# RDN_3103.net
KiCad netlist of a schematic drawn in EAGLE
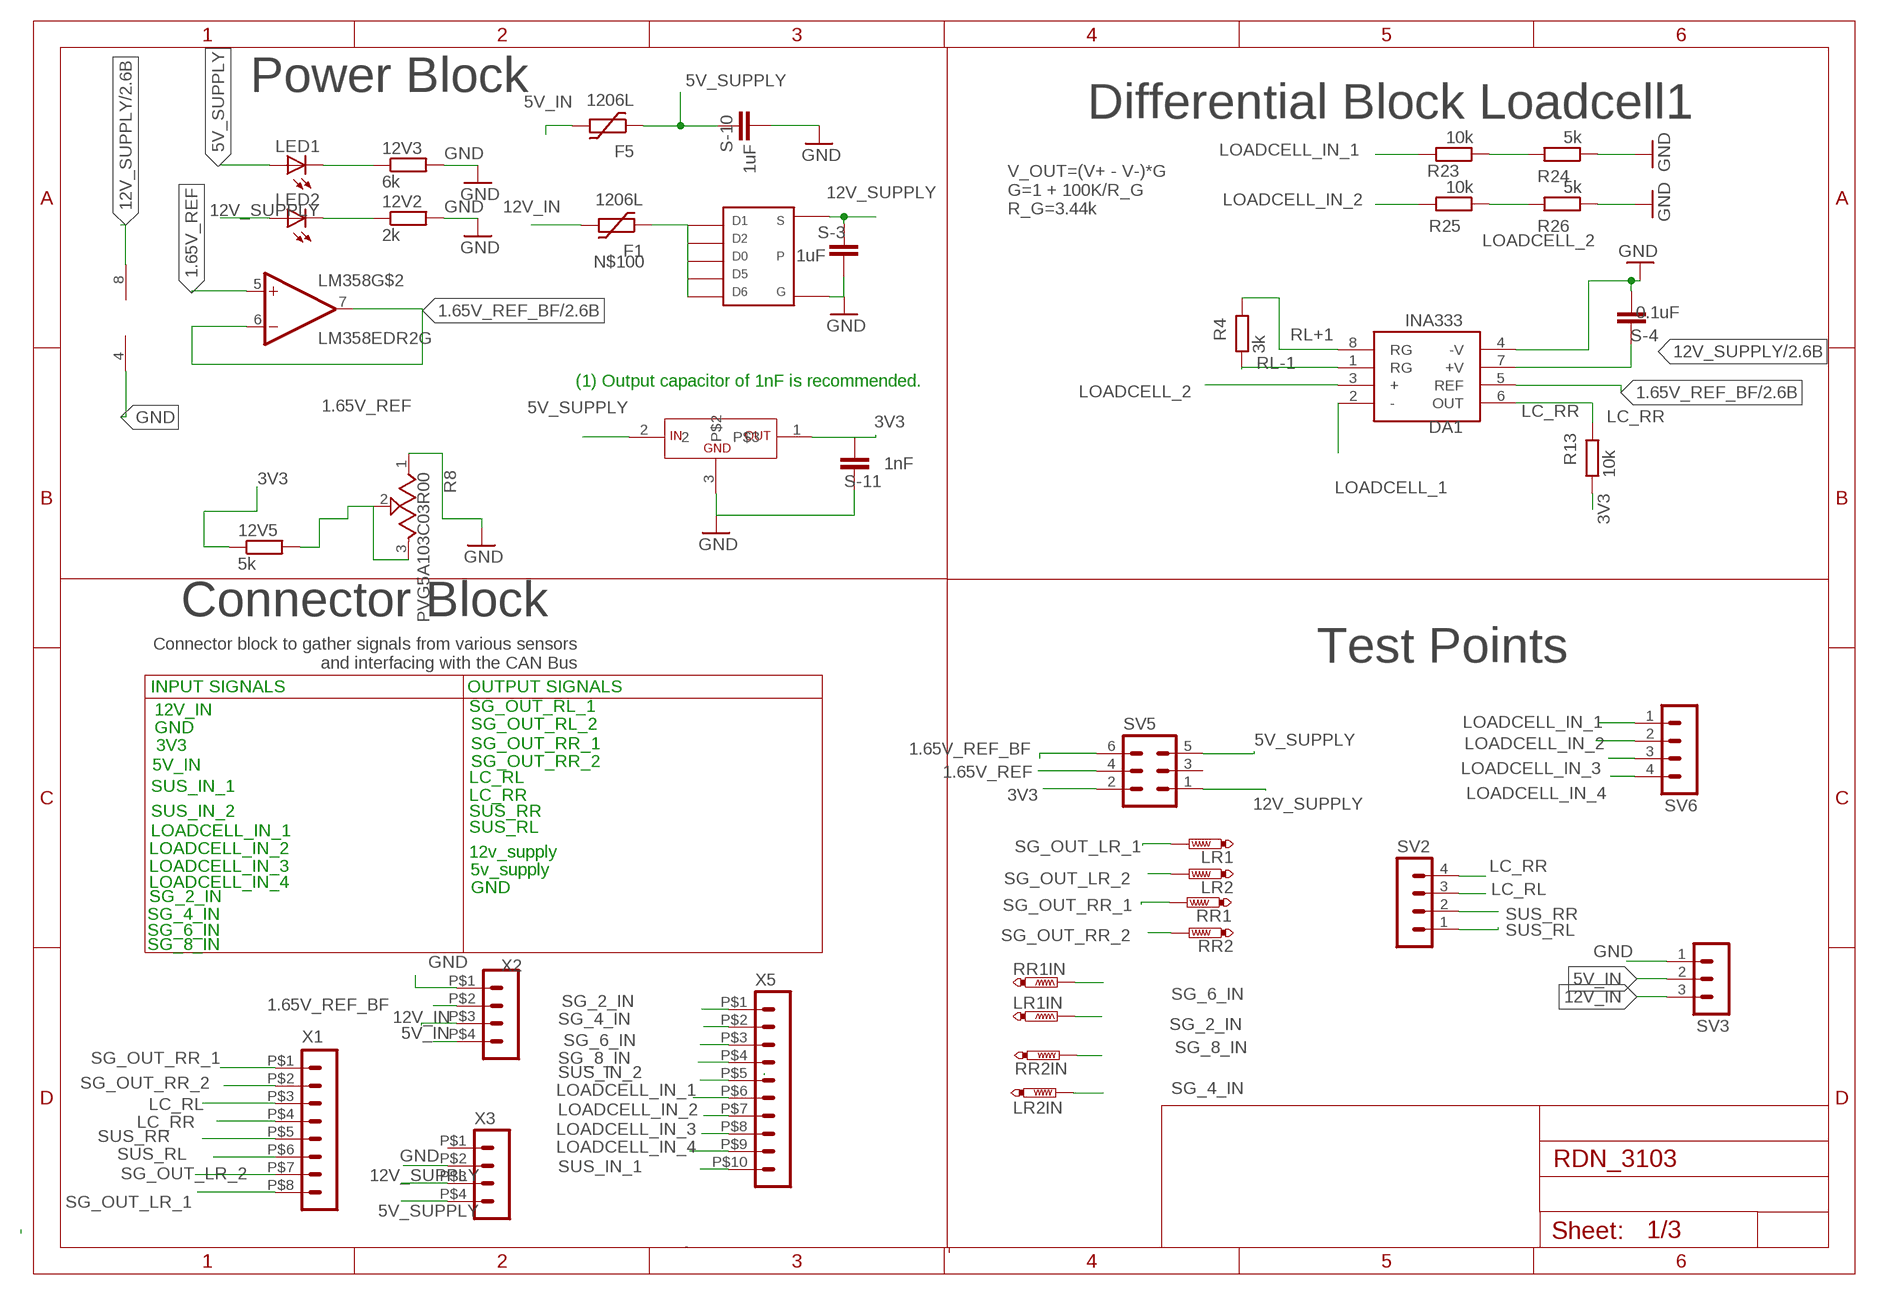
[diagram p0: schematic, sheet 1]
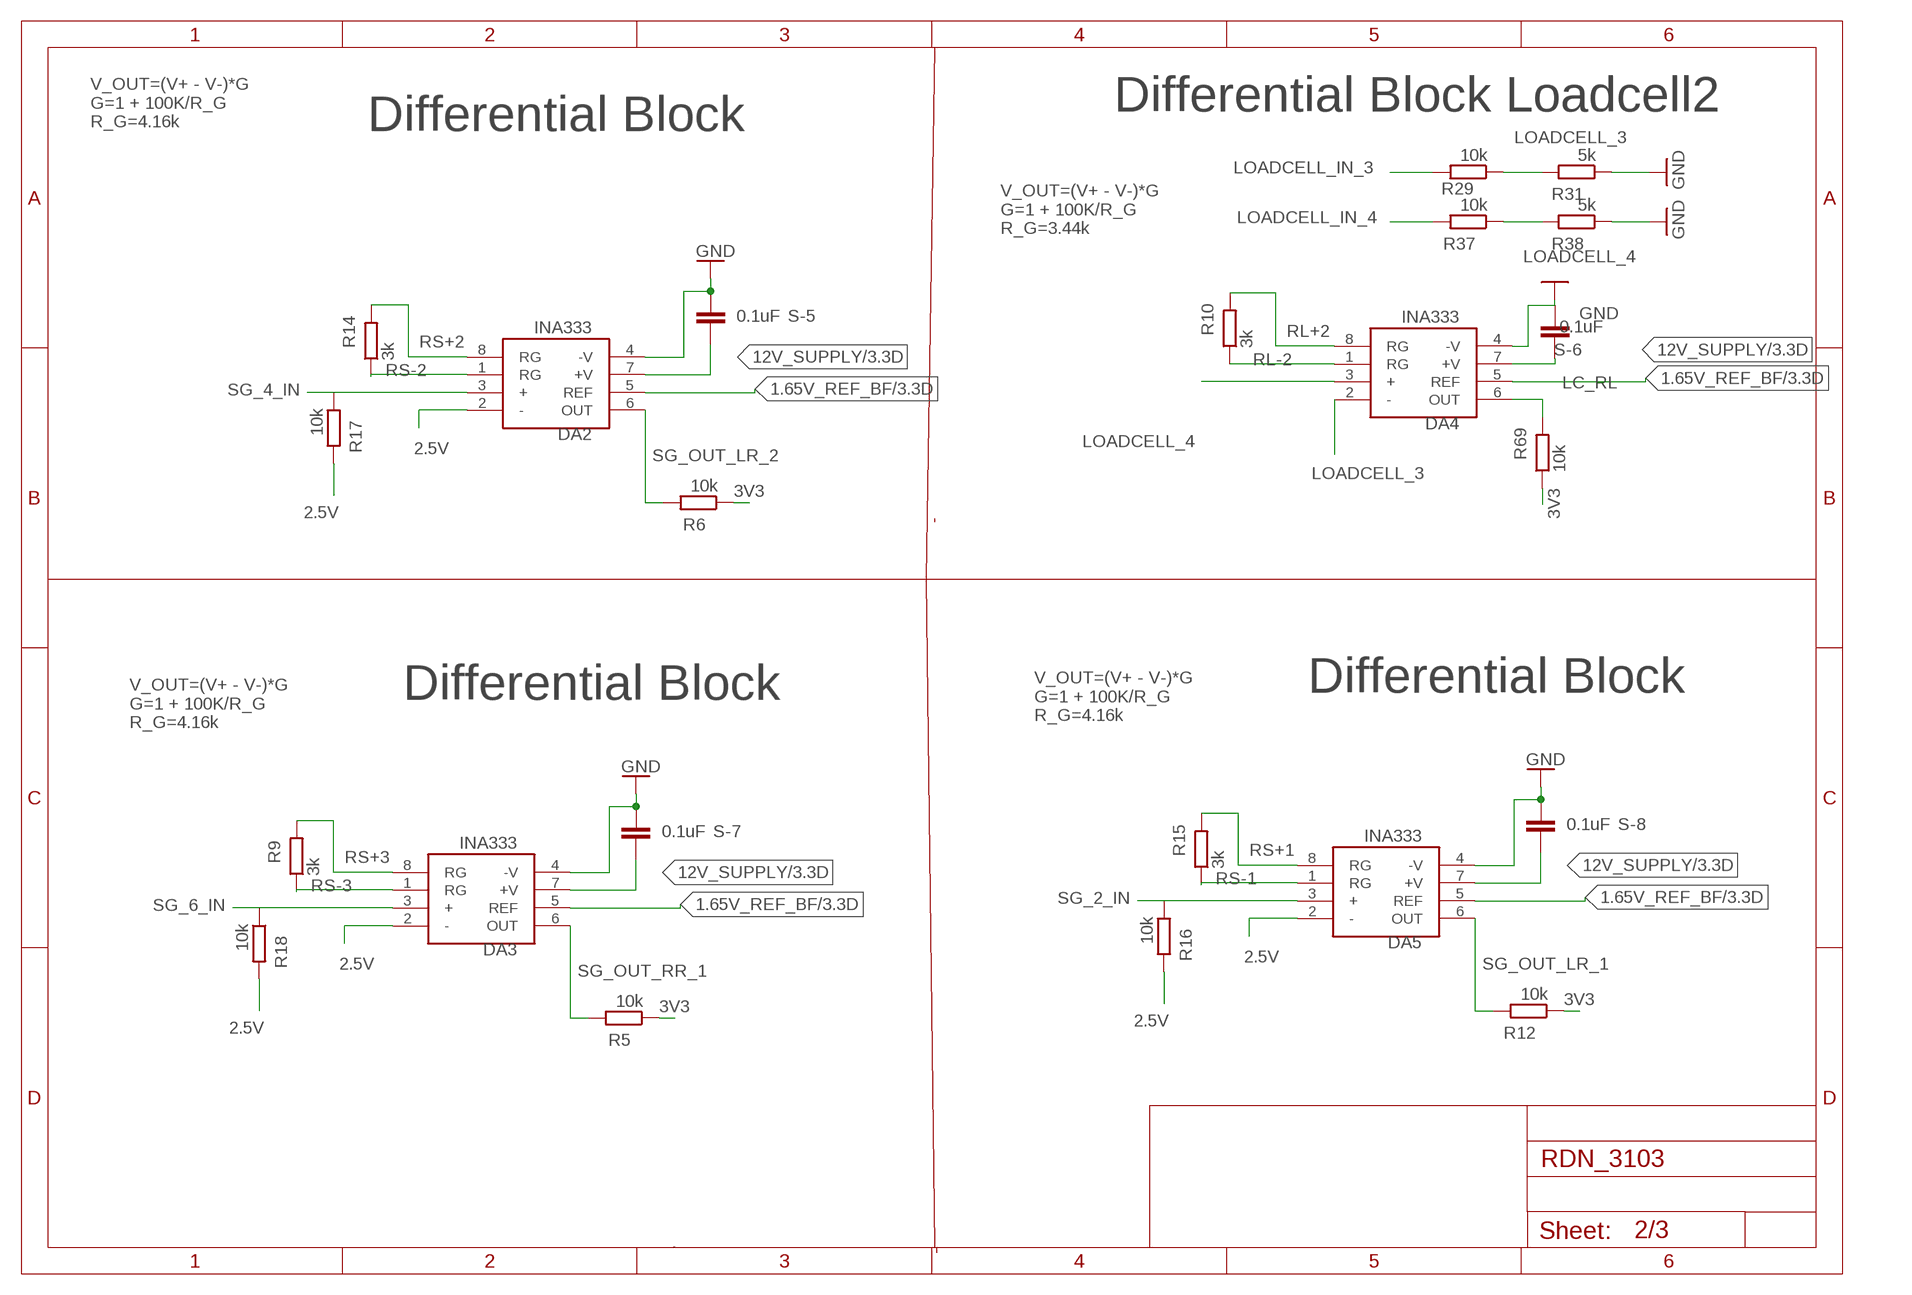
[diagram p1: schematic, sheet 2]
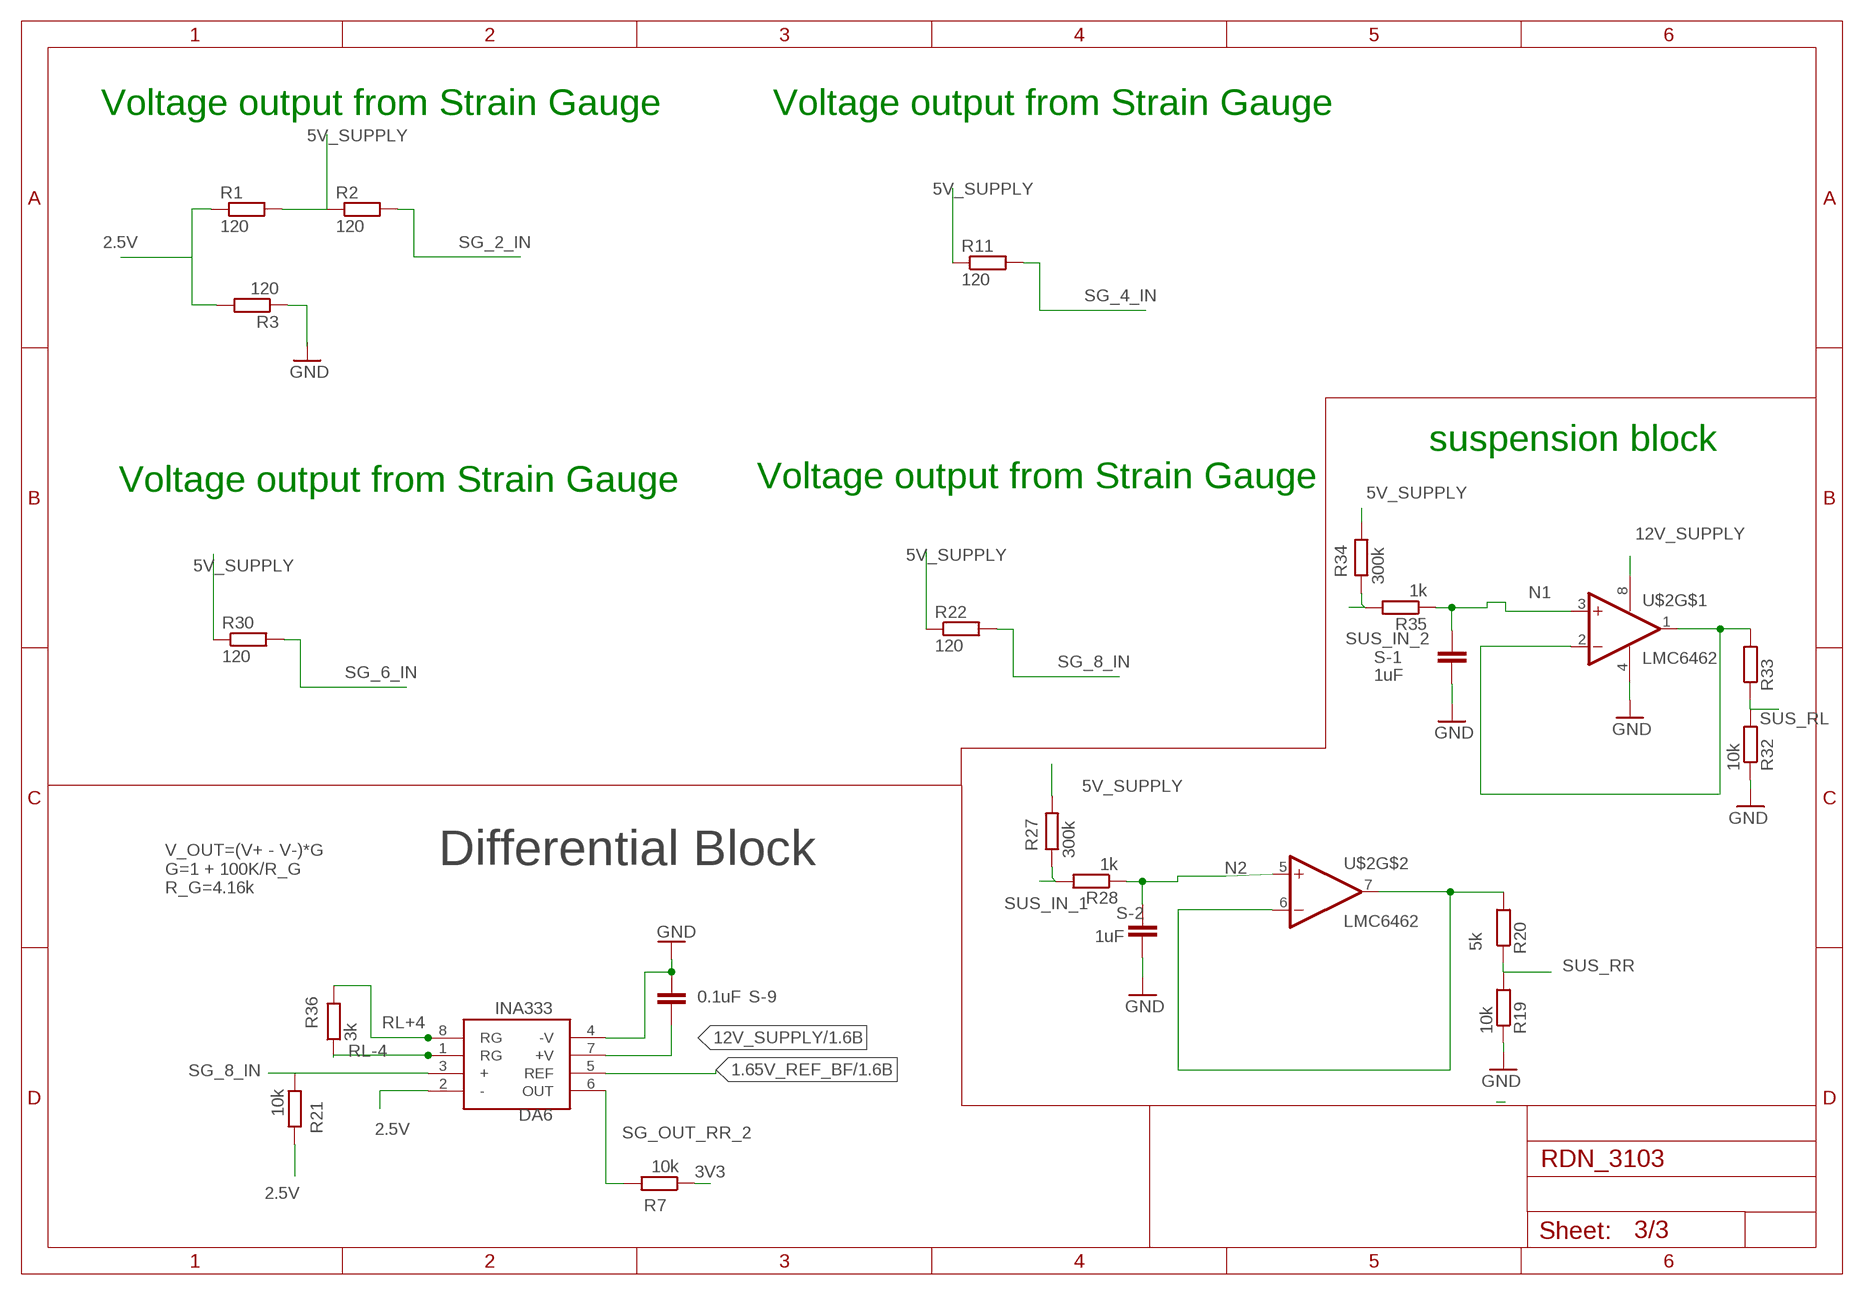
[diagram p2: schematic, sheet 3]

(export (version "E")
  (design (tool "Eeschema 10.0.6"))
  (components
    (comp (ref "DA2")
      (value "INA333")
      (footprint "eagle-import:MSOP8")
      (fields (field (name "MF") "Texas Instruments"))
      (libsource (lib "eagle-import") (part "INA333"))
    )
    (comp (ref "DA3")
      (value "INA333")
      (footprint "eagle-import:MSOP8")
      (fields (field (name "MF") "Texas Instruments"))
      (libsource (lib "eagle-import") (part "INA333"))
    )
    (comp (ref "DA4")
      (value "INA333")
      (footprint "eagle-import:MSOP8")
      (fields (field (name "MF") "Texas Instruments"))
      (libsource (lib "eagle-import") (part "INA333"))
    )
    (comp (ref "DA5")
      (value "INA333")
      (footprint "eagle-import:MSOP8")
      (fields (field (name "MF") "Texas Instruments"))
      (libsource (lib "eagle-import") (part "INA333"))
    )
    (comp (ref "R5")
      (value "10k")
      (footprint "eagle-import:R0805")
      (libsource (lib "eagle-import") (part "R-EU_R0805"))
    )
    (comp (ref "R6")
      (value "10k")
      (footprint "eagle-import:R0805")
      (libsource (lib "eagle-import") (part "R-EU_R0805"))
    )
    (comp (ref "R9")
      (value "3k")
      (footprint "eagle-import:R0805")
      (libsource (lib "eagle-import") (part "R-EU_R0805"))
    )
    (comp (ref "R10")
      (value "3k")
      (footprint "eagle-import:R0805")
      (libsource (lib "eagle-import") (part "R-EU_R0805"))
    )
    (comp (ref "R12")
      (value "10k")
      (footprint "eagle-import:R0805")
      (libsource (lib "eagle-import") (part "R-EU_R0805"))
    )
    (comp (ref "R14")
      (value "3k")
      (footprint "eagle-import:R0805")
      (libsource (lib "eagle-import") (part "R-EU_R0805"))
    )
    (comp (ref "R15")
      (value "3k")
      (footprint "eagle-import:R0805")
      (libsource (lib "eagle-import") (part "R-EU_R0805"))
    )
    (comp (ref "R16")
      (value "10k")
      (footprint "eagle-import:R0805")
      (libsource (lib "eagle-import") (part "R-EU_R0805"))
    )
    (comp (ref "R17")
      (value "10k")
      (footprint "eagle-import:R0805")
      (libsource (lib "eagle-import") (part "R-EU_R0805"))
    )
    (comp (ref "R18")
      (value "10k")
      (footprint "eagle-import:R0805")
      (libsource (lib "eagle-import") (part "R-EU_R0805"))
    )
    (comp (ref "R29")
      (value "10k")
      (footprint "eagle-import:R0805")
      (libsource (lib "eagle-import") (part "R-EU_R0805"))
    )
    (comp (ref "R31")
      (value "5k")
      (footprint "eagle-import:R0805")
      (libsource (lib "eagle-import") (part "R-EU_R0805"))
    )
    (comp (ref "R37")
      (value "10k")
      (footprint "eagle-import:R0805")
      (libsource (lib "eagle-import") (part "R-EU_R0805"))
    )
    (comp (ref "R38")
      (value "5k")
      (footprint "eagle-import:R0805")
      (libsource (lib "eagle-import") (part "R-EU_R0805"))
    )
    (comp (ref "R69")
      (value "10k")
      (footprint "eagle-import:R0805")
      (libsource (lib "eagle-import") (part "R-EU_R0805"))
    )
    (comp (ref "S-5")
      (value "0.1uF")
      (footprint "eagle-import:C0805")
      (libsource (lib "eagle-import") (part "C-EUC0805"))
    )
    (comp (ref "S-6")
      (value "0.1uF")
      (footprint "eagle-import:C0805")
      (libsource (lib "eagle-import") (part "C-EUC0805"))
    )
    (comp (ref "S-7")
      (value "0.1uF")
      (footprint "eagle-import:C0805")
      (libsource (lib "eagle-import") (part "C-EUC0805"))
    )
    (comp (ref "S-8")
      (value "0.1uF")
      (footprint "eagle-import:C0805")
      (libsource (lib "eagle-import") (part "C-EUC0805"))
    )
    (comp (ref "12V2")
      (value "2k")
      (footprint "eagle-import:R0805")
      (libsource (lib "eagle-import") (part "rcl_R-EU_R0805"))
    )
    (comp (ref "12V3")
      (value "6k")
      (footprint "eagle-import:R0805")
      (libsource (lib "eagle-import") (part "rcl_R-EU_R0805"))
    )
    (comp (ref "12V5")
      (value "5k")
      (footprint "eagle-import:R0805")
      (libsource (lib "eagle-import") (part "rcl_R-EU_R0805"))
    )
    (comp (ref "DA1")
      (value "INA333")
      (footprint "eagle-import:MSOP8")
      (fields (field (name "MF") "Texas Instruments"))
      (libsource (lib "eagle-import") (part "INA333"))
    )
    (comp (ref "F1")
      (value "1206L")
      (footprint "eagle-import:1206L")
      (libsource (lib "eagle-import") (part "1206L"))
    )
    (comp (ref "F5")
      (value "1206L")
      (footprint "eagle-import:1206L")
      (libsource (lib "eagle-import") (part "1206L"))
    )
    (comp (ref "LED1")
      (value "LEDCHIPLED_1206")
      (footprint "eagle-import:CHIPLED_1206")
      (libsource (lib "eagle-import") (part "LEDCHIPLED_1206"))
    )
    (comp (ref "LED2")
      (value "LEDCHIPLED_1206")
      (footprint "eagle-import:CHIPLED_1206")
      (fields (field (name "SPICEPREFIX") "L"))
      (libsource (lib "eagle-import") (part "LEDCHIPLED_1206"))
    )
    (comp (ref "LM358")
      (value "LM358EDR2G")
      (footprint "eagle-import:SOIC-8")
      (libsource (lib "eagle-import") (part "LM358EDR2G"))
    )
    (comp (ref "LR1")
      (value "PTR1PAD1-13")
      (footprint "eagle-import:P1-13")
      (libsource (lib "eagle-import") (part "PTR1PAD1-13"))
    )
    (comp (ref "LR1IN")
      (value "PTR1PAD1-13")
      (footprint "eagle-import:P1-13")
      (libsource (lib "eagle-import") (part "PTR1PAD1-13"))
    )
    (comp (ref "LR2")
      (value "PTR1PAD1-13")
      (footprint "eagle-import:P1-13")
      (libsource (lib "eagle-import") (part "PTR1PAD1-13"))
    )
    (comp (ref "LR2IN")
      (value "PTR1PAD1-13")
      (footprint "eagle-import:P1-13")
      (libsource (lib "eagle-import") (part "PTR1PAD1-13"))
    )
    (comp (ref "R4")
      (value "3k")
      (footprint "eagle-import:R0805")
      (libsource (lib "eagle-import") (part "R-EU_R0805"))
    )
    (comp (ref "R8")
      (value "PVG5A103C03R00")
      (footprint "eagle-import:TRIM_PVG5A103C03R00")
      (fields (field (name "MF") "Bourns"))
      (libsource (lib "eagle-import") (part "PVG5A103C03R00"))
    )
    (comp (ref "R13")
      (value "10k")
      (footprint "eagle-import:R0805")
      (libsource (lib "eagle-import") (part "R-EU_R0805"))
    )
    (comp (ref "R23")
      (value "10k")
      (footprint "eagle-import:R0805")
      (libsource (lib "eagle-import") (part "R-EU_R0805"))
    )
    (comp (ref "R24")
      (value "5k")
      (footprint "eagle-import:R0805")
      (libsource (lib "eagle-import") (part "R-EU_R0805"))
    )
    (comp (ref "R25")
      (value "10k")
      (footprint "eagle-import:R0805")
      (libsource (lib "eagle-import") (part "R-EU_R0805"))
    )
    (comp (ref "R26")
      (value "5k")
      (footprint "eagle-import:R0805")
      (libsource (lib "eagle-import") (part "R-EU_R0805"))
    )
    (comp (ref "RR1")
      (value "PTR1PAD1-13")
      (footprint "eagle-import:P1-13")
      (libsource (lib "eagle-import") (part "PTR1PAD1-13"))
    )
    (comp (ref "RR1IN")
      (value "PTR1PAD1-13")
      (footprint "eagle-import:P1-13")
      (libsource (lib "eagle-import") (part "PTR1PAD1-13"))
    )
    (comp (ref "RR2")
      (value "PTR1PAD1-13")
      (footprint "eagle-import:P1-13")
      (libsource (lib "eagle-import") (part "PTR1PAD1-13"))
    )
    (comp (ref "RR2IN")
      (value "PTR1PAD1-13")
      (footprint "eagle-import:P1-13")
      (libsource (lib "eagle-import") (part "PTR1PAD1-13"))
    )
    (comp (ref "S-3")
      (value "1uF")
      (footprint "eagle-import:C0805")
      (libsource (lib "eagle-import") (part "C-EUC0805"))
    )
    (comp (ref "S-4")
      (value "0.1uF")
      (footprint "eagle-import:C0805")
      (libsource (lib "eagle-import") (part "C-EUC0805"))
    )
    (comp (ref "S-10")
      (value "1uF")
      (footprint "eagle-import:C0805")
      (libsource (lib "eagle-import") (part "C-EUC0805"))
    )
    (comp (ref "S-11")
      (value "1nF")
      (footprint "eagle-import:C0805")
      (libsource (lib "eagle-import") (part "C-EUC0805"))
    )
    (comp (ref "SV2")
      (value "MA04-1")
      (footprint "eagle-import:MA04-1")
      (libsource (lib "eagle-import") (part "MA04-1"))
    )
    (comp (ref "SV3")
      (value "MA03-1")
      (footprint "eagle-import:MA03-1")
      (libsource (lib "eagle-import") (part "MA03-1"))
    )
    (comp (ref "SV5")
      (value "MA03-2")
      (footprint "eagle-import:MA03-2")
      (libsource (lib "eagle-import") (part "MA03-2"))
    )
    (comp (ref "SV6")
      (value "MA04-1")
      (footprint "eagle-import:MA04-1")
      (libsource (lib "eagle-import") (part "MA04-1"))
    )
    (comp (ref "U$1")
      (value "TSOP-6_PMOS")
      (footprint "eagle-import:TSOP-6_PMOS")
      (libsource (lib "eagle-import") (part "TSOP-6_PMOS"))
    )
    (comp (ref "U$3")
      (value "3V3_REGULATOR")
      (footprint "eagle-import:SOT-23")
      (libsource (lib "eagle-import") (part "3V3_REGULATOR"))
    )
    (comp (ref "X1")
      (value "HEADER_POS8_43045-0800")
      (footprint "eagle-import:43045-0800")
      (libsource (lib "eagle-import") (part "HEADER_POS8_?43045-0800"))
    )
    (comp (ref "X2")
      (value "HEADER_POS4_43045-0401")
      (footprint "eagle-import:43045-0400")
      (libsource (lib "eagle-import") (part "HEADER_POS4_?43045-0401"))
    )
    (comp (ref "X3")
      (value "HEADER_POS4_43045-0401")
      (footprint "eagle-import:43045-0400")
      (libsource (lib "eagle-import") (part "HEADER_POS4_?43045-0401"))
    )
    (comp (ref "X5")
      (value "HEADER_POS10_43045-1000")
      (footprint "eagle-import:43045-1000")
      (libsource (lib "eagle-import") (part "HEADER_POS10_?43045-1000"))
    )
    (comp (ref "DA6")
      (value "INA333")
      (footprint "eagle-import:MSOP8")
      (fields (field (name "MF") "Texas Instruments"))
      (libsource (lib "eagle-import") (part "INA333"))
    )
    (comp (ref "R1")
      (value "120")
      (footprint "eagle-import:R0805")
      (libsource (lib "eagle-import") (part "rcl_R-EU_R0805"))
    )
    (comp (ref "R2")
      (value "120")
      (footprint "eagle-import:R0805")
      (libsource (lib "eagle-import") (part "rcl_R-EU_R0805"))
    )
    (comp (ref "R3")
      (value "120")
      (footprint "eagle-import:R0805")
      (libsource (lib "eagle-import") (part "rcl_R-EU_R0805"))
    )
    (comp (ref "R7")
      (value "10k")
      (footprint "eagle-import:R0805")
      (libsource (lib "eagle-import") (part "R-EU_R0805"))
    )
    (comp (ref "R11")
      (value "120")
      (footprint "eagle-import:R0805")
      (libsource (lib "eagle-import") (part "rcl_R-EU_R0805"))
    )
    (comp (ref "R19")
      (value "10k")
      (footprint "eagle-import:R0805")
      (libsource (lib "eagle-import") (part "IIT_BOMBAY_Racing2_R-EU_R0805"))
    )
    (comp (ref "R20")
      (value "5k")
      (footprint "eagle-import:R0805")
      (libsource (lib "eagle-import") (part "IIT_BOMBAY_Racing2_R-EU_R0805"))
    )
    (comp (ref "R21")
      (value "10k")
      (footprint "eagle-import:R0805")
      (libsource (lib "eagle-import") (part "R-EU_R0805"))
    )
    (comp (ref "R22")
      (value "120")
      (footprint "eagle-import:R0805")
      (libsource (lib "eagle-import") (part "rcl_R-EU_R0805"))
    )
    (comp (ref "R27")
      (value "300k")
      (footprint "eagle-import:R0805")
      (libsource (lib "eagle-import") (part "IIT_BOMBAY_Racing2_R-EU_R0805"))
    )
    (comp (ref "R28")
      (value "1k")
      (footprint "eagle-import:R0805")
      (libsource (lib "eagle-import") (part "IIT_BOMBAY_Racing2_R-EU_R0805"))
    )
    (comp (ref "R30")
      (value "120")
      (footprint "eagle-import:R0805")
      (libsource (lib "eagle-import") (part "rcl_R-EU_R0805"))
    )
    (comp (ref "R32")
      (value "10k")
      (footprint "eagle-import:R0805")
      (libsource (lib "eagle-import") (part "IIT_BOMBAY_Racing2_R-EU_R0805"))
    )
    (comp (ref "R33")
      (value "5k")
      (footprint "eagle-import:R0805")
      (libsource (lib "eagle-import") (part "IIT_BOMBAY_Racing2_R-EU_R0805"))
    )
    (comp (ref "R34")
      (value "300k")
      (footprint "eagle-import:R0805")
      (libsource (lib "eagle-import") (part "IIT_BOMBAY_Racing2_R-EU_R0805"))
    )
    (comp (ref "R35")
      (value "1k")
      (footprint "eagle-import:R0805")
      (libsource (lib "eagle-import") (part "IIT_BOMBAY_Racing2_R-EU_R0805"))
    )
    (comp (ref "R36")
      (value "3k")
      (footprint "eagle-import:R0805")
      (libsource (lib "eagle-import") (part "R-EU_R0805"))
    )
    (comp (ref "S-1")
      (value "1uF")
      (footprint "eagle-import:C0805")
      (libsource (lib "eagle-import") (part "C-EUC0805"))
    )
    (comp (ref "S-2")
      (value "1uF")
      (footprint "eagle-import:C0805")
      (libsource (lib "eagle-import") (part "C-EUC0805"))
    )
    (comp (ref "S-9")
      (value "0.1uF")
      (footprint "eagle-import:C0805")
      (libsource (lib "eagle-import") (part "C-EUC0805"))
    )
    (comp (ref "U$2")
      (value "LMC6462")
      (footprint "eagle-import:S08")
      (libsource (lib "eagle-import") (part "LMC6462"))
    )
  )
  (nets
    (net (code "1") (name "1.65V_REF") (class "Default")
      (node (ref "12V5") (pin "2") (pinfunction "2_2") (pintype "passive"))
      (node (ref "LM358") (pin "5") (pinfunction "+IN_5") (pintype "input"))
      (node (ref "R8") (pin "2") (pinfunction "2_2") (pintype "passive"))
      (node (ref "R8") (pin "3") (pinfunction "3_3") (pintype "passive"))
      (node (ref "SV5") (pin "4") (pinfunction "4_4") (pintype "passive"))
    )
    (net (code "2") (name "1.65V_REF_BF") (class "Default")
      (node (ref "DA1") (pin "5") (pinfunction "REF_5") (pintype "bidirectional"))
      (node (ref "DA2") (pin "5") (pinfunction "REF_5") (pintype "bidirectional"))
      (node (ref "DA3") (pin "5") (pinfunction "REF_5") (pintype "bidirectional"))
      (node (ref "DA4") (pin "5") (pinfunction "REF_5") (pintype "bidirectional"))
      (node (ref "DA5") (pin "5") (pinfunction "REF_5") (pintype "bidirectional"))
      (node (ref "DA6") (pin "5") (pinfunction "REF_5") (pintype "bidirectional"))
      (node (ref "LM358") (pin "6") (pinfunction "-IN_6") (pintype "input"))
      (node (ref "LM358") (pin "7") (pinfunction "OUT_7") (pintype "output"))
      (node (ref "SV5") (pin "6") (pinfunction "6_6") (pintype "passive"))
      (node (ref "X2") (pin "P$2") (pinfunction "2_P$2") (pintype "passive"))
    )
    (net (code "3") (name "2.5V") (class "Default")
      (node (ref "DA2") (pin "2") (pinfunction "-_2") (pintype "bidirectional"))
      (node (ref "DA3") (pin "2") (pinfunction "-_2") (pintype "bidirectional"))
      (node (ref "DA5") (pin "2") (pinfunction "-_2") (pintype "bidirectional"))
      (node (ref "DA6") (pin "2") (pinfunction "-_2") (pintype "bidirectional"))
      (node (ref "R1") (pin "1") (pinfunction "1_1") (pintype "passive"))
      (node (ref "R16") (pin "2") (pinfunction "2_2") (pintype "passive"))
      (node (ref "R17") (pin "2") (pinfunction "2_2") (pintype "passive"))
      (node (ref "R18") (pin "2") (pinfunction "2_2") (pintype "passive"))
      (node (ref "R21") (pin "2") (pinfunction "2_2") (pintype "passive"))
      (node (ref "R3") (pin "2") (pinfunction "2_2") (pintype "passive"))
    )
    (net (code "4") (name "3V3") (class "Default")
      (node (ref "12V5") (pin "1") (pinfunction "1_1") (pintype "passive"))
      (node (ref "R12") (pin "1") (pinfunction "1_1") (pintype "passive"))
      (node (ref "R13") (pin "1") (pinfunction "1_1") (pintype "passive"))
      (node (ref "R5") (pin "1") (pinfunction "1_1") (pintype "passive"))
      (node (ref "R6") (pin "1") (pinfunction "1_1") (pintype "passive"))
      (node (ref "R69") (pin "1") (pinfunction "1_1") (pintype "passive"))
      (node (ref "R7") (pin "1") (pinfunction "1_1") (pintype "passive"))
      (node (ref "S-11") (pin "2") (pinfunction "2_2") (pintype "passive"))
      (node (ref "SV5") (pin "2") (pinfunction "2_2") (pintype "passive"))
      (node (ref "U$3") (pin "1") (pinfunction "P$3_1") (pintype "bidirectional"))
    )
    (net (code "5") (name "5V_IN") (class "Default")
      (node (ref "F5") (pin "P$2") (pinfunction "2_P$2") (pintype "passive"))
      (node (ref "SV3") (pin "2") (pinfunction "2_2") (pintype "passive"))
      (node (ref "X2") (pin "P$4") (pinfunction "4_P$4") (pintype "passive"))
    )
    (net (code "6") (name "5V_SUPPLY") (class "Default")
      (node (ref "F5") (pin "P$1") (pinfunction "1_P$1") (pintype "passive"))
      (node (ref "LED1") (pin "A") (pinfunction "A_A") (pintype "passive"))
      (node (ref "R1") (pin "2") (pinfunction "2_2") (pintype "passive"))
      (node (ref "R11") (pin "1") (pinfunction "1_1") (pintype "passive"))
      (node (ref "R2") (pin "1") (pinfunction "1_1") (pintype "passive"))
      (node (ref "R22") (pin "1") (pinfunction "1_1") (pintype "passive"))
      (node (ref "R27") (pin "2") (pinfunction "2_2") (pintype "passive"))
      (node (ref "R30") (pin "1") (pinfunction "1_1") (pintype "passive"))
      (node (ref "R34") (pin "2") (pinfunction "2_2") (pintype "passive"))
      (node (ref "S-10") (pin "1") (pinfunction "1_1") (pintype "passive"))
      (node (ref "SV5") (pin "5") (pinfunction "5_5") (pintype "passive"))
      (node (ref "U$3") (pin "2") (pinfunction "2_2") (pintype "bidirectional"))
      (node (ref "X3") (pin "P$4") (pinfunction "4_P$4") (pintype "passive"))
    )
    (net (code "7") (name "12V_IN") (class "Default")
      (node (ref "F1") (pin "P$2") (pinfunction "2_P$2") (pintype "passive"))
      (node (ref "SV3") (pin "3") (pinfunction "3_3") (pintype "passive"))
      (node (ref "X2") (pin "P$3") (pinfunction "3_P$3") (pintype "passive"))
    )
    (net (code "8") (name "12V_SUPPLY") (class "Default")
      (node (ref "DA1") (pin "7") (pinfunction "+V_7") (pintype "bidirectional"))
      (node (ref "DA2") (pin "7") (pinfunction "+V_7") (pintype "bidirectional"))
      (node (ref "DA3") (pin "7") (pinfunction "+V_7") (pintype "bidirectional"))
      (node (ref "DA4") (pin "7") (pinfunction "+V_7") (pintype "bidirectional"))
      (node (ref "DA5") (pin "7") (pinfunction "+V_7") (pintype "bidirectional"))
      (node (ref "DA6") (pin "7") (pinfunction "+V_7") (pintype "bidirectional"))
      (node (ref "LED2") (pin "A") (pinfunction "A_A") (pintype "passive"))
      (node (ref "LM358") (pin "8") (pinfunction "V+_8") (pintype "power_in"))
      (node (ref "S-3") (pin "1") (pinfunction "1_1") (pintype "passive"))
      (node (ref "S-4") (pin "1") (pinfunction "1_1") (pintype "passive"))
      (node (ref "S-5") (pin "1") (pinfunction "1_1") (pintype "passive"))
      (node (ref "S-6") (pin "1") (pinfunction "1_1") (pintype "passive"))
      (node (ref "S-7") (pin "1") (pinfunction "1_1") (pintype "passive"))
      (node (ref "S-8") (pin "1") (pinfunction "1_1") (pintype "passive"))
      (node (ref "S-9") (pin "1") (pinfunction "1_1") (pintype "passive"))
      (node (ref "SV5") (pin "1") (pinfunction "1_1") (pintype "passive"))
      (node (ref "U$1") (pin "S") (pinfunction "S_S") (pintype "bidirectional"))
      (node (ref "U$2") (pin "8") (pinfunction "V+_8") (pintype "power_in"))
      (node (ref "X3") (pin "P$3") (pinfunction "3_P$3") (pintype "passive"))
    )
    (net (code "9") (name "GND") (class "Default")
      (node (ref "12V2") (pin "2") (pinfunction "2_2") (pintype "passive"))
      (node (ref "12V3") (pin "2") (pinfunction "2_2") (pintype "passive"))
      (node (ref "DA1") (pin "4") (pinfunction "-V_4") (pintype "bidirectional"))
      (node (ref "DA2") (pin "4") (pinfunction "-V_4") (pintype "bidirectional"))
      (node (ref "DA3") (pin "4") (pinfunction "-V_4") (pintype "bidirectional"))
      (node (ref "DA4") (pin "4") (pinfunction "-V_4") (pintype "bidirectional"))
      (node (ref "DA5") (pin "4") (pinfunction "-V_4") (pintype "bidirectional"))
      (node (ref "DA6") (pin "4") (pinfunction "-V_4") (pintype "bidirectional"))
      (node (ref "LM358") (pin "4") (pinfunction "V-_4") (pintype "power_in"))
      (node (ref "R19") (pin "1") (pinfunction "1_1") (pintype "passive"))
      (node (ref "R24") (pin "1") (pinfunction "1_1") (pintype "passive"))
      (node (ref "R26") (pin "1") (pinfunction "1_1") (pintype "passive"))
      (node (ref "R3") (pin "1") (pinfunction "1_1") (pintype "passive"))
      (node (ref "R31") (pin "1") (pinfunction "1_1") (pintype "passive"))
      (node (ref "R32") (pin "1") (pinfunction "1_1") (pintype "passive"))
      (node (ref "R38") (pin "1") (pinfunction "1_1") (pintype "passive"))
      (node (ref "R8") (pin "1") (pinfunction "1_1") (pintype "passive"))
      (node (ref "S-1") (pin "2") (pinfunction "2_2") (pintype "passive"))
      (node (ref "S-10") (pin "2") (pinfunction "2_2") (pintype "passive"))
      (node (ref "S-11") (pin "1") (pinfunction "1_1") (pintype "passive"))
      (node (ref "S-2") (pin "2") (pinfunction "2_2") (pintype "passive"))
      (node (ref "S-3") (pin "2") (pinfunction "2_2") (pintype "passive"))
      (node (ref "S-4") (pin "2") (pinfunction "2_2") (pintype "passive"))
      (node (ref "S-5") (pin "2") (pinfunction "2_2") (pintype "passive"))
      (node (ref "S-6") (pin "2") (pinfunction "2_2") (pintype "passive"))
      (node (ref "S-7") (pin "2") (pinfunction "2_2") (pintype "passive"))
      (node (ref "S-8") (pin "2") (pinfunction "2_2") (pintype "passive"))
      (node (ref "S-9") (pin "2") (pinfunction "2_2") (pintype "passive"))
      (node (ref "SV3") (pin "1") (pinfunction "1_1") (pintype "passive"))
      (node (ref "U$1") (pin "G") (pinfunction "G_G") (pintype "bidirectional"))
      (node (ref "U$2") (pin "4") (pinfunction "V-_4") (pintype "power_in"))
      (node (ref "U$3") (pin "3") (pinfunction "P$2_3") (pintype "bidirectional"))
      (node (ref "X2") (pin "P$1") (pinfunction "1_P$1") (pintype "passive"))
      (node (ref "X3") (pin "P$2") (pinfunction "2_P$2") (pintype "passive"))
    )
    (net (code "10") (name "LC_RL") (class "Default")
      (node (ref "DA4") (pin "6") (pinfunction "OUT_6") (pintype "bidirectional"))
      (node (ref "R69") (pin "2") (pinfunction "2_2") (pintype "passive"))
      (node (ref "SV2") (pin "3") (pinfunction "3_3") (pintype "passive"))
      (node (ref "X1") (pin "P$3") (pinfunction "3_P$3") (pintype "passive"))
    )
    (net (code "11") (name "LC_RR") (class "Default")
      (node (ref "DA1") (pin "6") (pinfunction "OUT_6") (pintype "bidirectional"))
      (node (ref "R13") (pin "2") (pinfunction "2_2") (pintype "passive"))
      (node (ref "SV2") (pin "4") (pinfunction "4_4") (pintype "passive"))
      (node (ref "X1") (pin "P$4") (pinfunction "4_P$4") (pintype "passive"))
    )
    (net (code "12") (name "LOADCELL_1") (class "Default")
      (node (ref "DA1") (pin "2") (pinfunction "-_2") (pintype "bidirectional"))
      (node (ref "R23") (pin "1") (pinfunction "1_1") (pintype "passive"))
      (node (ref "R24") (pin "2") (pinfunction "2_2") (pintype "passive"))
    )
    (net (code "13") (name "LOADCELL_2") (class "Default")
      (node (ref "DA1") (pin "3") (pinfunction "+_3") (pintype "bidirectional"))
      (node (ref "R25") (pin "1") (pinfunction "1_1") (pintype "passive"))
      (node (ref "R26") (pin "2") (pinfunction "2_2") (pintype "passive"))
    )
    (net (code "14") (name "LOADCELL_3") (class "Default")
      (node (ref "DA4") (pin "2") (pinfunction "-_2") (pintype "bidirectional"))
      (node (ref "R29") (pin "1") (pinfunction "1_1") (pintype "passive"))
      (node (ref "R31") (pin "2") (pinfunction "2_2") (pintype "passive"))
    )
    (net (code "15") (name "LOADCELL_4") (class "Default")
      (node (ref "DA4") (pin "3") (pinfunction "+_3") (pintype "bidirectional"))
      (node (ref "R37") (pin "1") (pinfunction "1_1") (pintype "passive"))
      (node (ref "R38") (pin "2") (pinfunction "2_2") (pintype "passive"))
    )
    (net (code "16") (name "LOADCELL_IN_1") (class "Default")
      (node (ref "R23") (pin "2") (pinfunction "2_2") (pintype "passive"))
      (node (ref "SV6") (pin "1") (pinfunction "1_1") (pintype "passive"))
      (node (ref "X5") (pin "P$6") (pinfunction "6_P$6") (pintype "passive"))
    )
    (net (code "17") (name "LOADCELL_IN_2") (class "Default")
      (node (ref "R25") (pin "2") (pinfunction "2_2") (pintype "passive"))
      (node (ref "SV6") (pin "2") (pinfunction "2_2") (pintype "passive"))
      (node (ref "X5") (pin "P$7") (pinfunction "7_P$7") (pintype "passive"))
    )
    (net (code "18") (name "LOADCELL_IN_3") (class "Default")
      (node (ref "R29") (pin "2") (pinfunction "2_2") (pintype "passive"))
      (node (ref "SV6") (pin "3") (pinfunction "3_3") (pintype "passive"))
      (node (ref "X5") (pin "P$8") (pinfunction "8_P$8") (pintype "passive"))
    )
    (net (code "19") (name "LOADCELL_IN_4") (class "Default")
      (node (ref "R37") (pin "2") (pinfunction "2_2") (pintype "passive"))
      (node (ref "SV6") (pin "4") (pinfunction "4_4") (pintype "passive"))
      (node (ref "X5") (pin "P$9") (pinfunction "9_P$9") (pintype "passive"))
    )
    (net (code "20") (name "N$100") (class "Default")
      (node (ref "F1") (pin "P$1") (pinfunction "1_P$1") (pintype "passive"))
      (node (ref "U$1") (pin "1") (pinfunction "1_1") (pintype "bidirectional"))
      (node (ref "U$1") (pin "2") (pinfunction "2_2") (pintype "bidirectional"))
      (node (ref "U$1") (pin "5") (pinfunction "5_5") (pintype "bidirectional"))
      (node (ref "U$1") (pin "6") (pinfunction "6_6") (pintype "bidirectional"))
      (node (ref "U$1") (pin "D") (pinfunction "D0_D") (pintype "bidirectional"))
    )
    (net (code "21") (name "N1") (class "Default")
      (node (ref "R35") (pin "1") (pinfunction "1_1") (pintype "passive"))
      (node (ref "S-1") (pin "1") (pinfunction "1_1") (pintype "passive"))
      (node (ref "U$2") (pin "3") (pinfunction "+IN_3") (pintype "input"))
    )
    (net (code "22") (name "N2") (class "Default")
      (node (ref "R28") (pin "1") (pinfunction "1_1") (pintype "passive"))
      (node (ref "S-2") (pin "1") (pinfunction "1_1") (pintype "passive"))
      (node (ref "U$2") (pin "5") (pinfunction "+IN_5") (pintype "input"))
    )
    (net (code "23") (name "Net-(12V2-Pad1)") (class "Default")
      (node (ref "12V2") (pin "1") (pinfunction "1_1") (pintype "passive"))
      (node (ref "LED2") (pin "C") (pinfunction "C_C") (pintype "passive"))
    )
    (net (code "24") (name "Net-(12V3-Pad1)") (class "Default")
      (node (ref "12V3") (pin "1") (pinfunction "1_1") (pintype "passive"))
      (node (ref "LED1") (pin "C") (pinfunction "C_C") (pintype "passive"))
    )
    (net (code "25") (name "Net-(U$2A--IN)") (class "Default")
      (node (ref "R33") (pin "2") (pinfunction "2_2") (pintype "passive"))
      (node (ref "U$2") (pin "1") (pinfunction "OUT_1") (pintype "output"))
      (node (ref "U$2") (pin "2") (pinfunction "-IN_2") (pintype "input"))
    )
    (net (code "26") (name "Net-(U$2B--IN)") (class "Default")
      (node (ref "R20") (pin "2") (pinfunction "2_2") (pintype "passive"))
      (node (ref "U$2") (pin "6") (pinfunction "-IN_6") (pintype "input"))
      (node (ref "U$2") (pin "7") (pinfunction "OUT_7") (pintype "output"))
    )
    (net (code "27") (name "RL+1") (class "Default")
      (node (ref "DA1") (pin "8") (pinfunction "RG_8") (pintype "bidirectional"))
      (node (ref "R4") (pin "2") (pinfunction "2_2") (pintype "passive"))
    )
    (net (code "28") (name "RL+2") (class "Default")
      (node (ref "DA4") (pin "8") (pinfunction "RG_8") (pintype "bidirectional"))
      (node (ref "R10") (pin "2") (pinfunction "2_2") (pintype "passive"))
    )
    (net (code "29") (name "RL+4") (class "Default")
      (node (ref "DA6") (pin "8") (pinfunction "RG_8") (pintype "bidirectional"))
      (node (ref "R36") (pin "2") (pinfunction "2_2") (pintype "passive"))
    )
    (net (code "30") (name "RL-1") (class "Default")
      (node (ref "DA1") (pin "1") (pinfunction "RG_1") (pintype "bidirectional"))
      (node (ref "R4") (pin "1") (pinfunction "1_1") (pintype "passive"))
    )
    (net (code "31") (name "RL-2") (class "Default")
      (node (ref "DA4") (pin "1") (pinfunction "RG_1") (pintype "bidirectional"))
      (node (ref "R10") (pin "1") (pinfunction "1_1") (pintype "passive"))
    )
    (net (code "32") (name "RL-4") (class "Default")
      (node (ref "DA6") (pin "1") (pinfunction "RG_1") (pintype "bidirectional"))
      (node (ref "R36") (pin "1") (pinfunction "1_1") (pintype "passive"))
    )
    (net (code "33") (name "RS+1") (class "Default")
      (node (ref "DA5") (pin "8") (pinfunction "RG_8") (pintype "bidirectional"))
      (node (ref "R15") (pin "2") (pinfunction "2_2") (pintype "passive"))
    )
    (net (code "34") (name "RS+2") (class "Default")
      (node (ref "DA2") (pin "8") (pinfunction "RG_8") (pintype "bidirectional"))
      (node (ref "R14") (pin "2") (pinfunction "2_2") (pintype "passive"))
    )
    (net (code "35") (name "RS+3") (class "Default")
      (node (ref "DA3") (pin "8") (pinfunction "RG_8") (pintype "bidirectional"))
      (node (ref "R9") (pin "2") (pinfunction "2_2") (pintype "passive"))
    )
    (net (code "36") (name "RS-1") (class "Default")
      (node (ref "DA5") (pin "1") (pinfunction "RG_1") (pintype "bidirectional"))
      (node (ref "R15") (pin "1") (pinfunction "1_1") (pintype "passive"))
    )
    (net (code "37") (name "RS-2") (class "Default")
      (node (ref "DA2") (pin "1") (pinfunction "RG_1") (pintype "bidirectional"))
      (node (ref "R14") (pin "1") (pinfunction "1_1") (pintype "passive"))
    )
    (net (code "38") (name "RS-3") (class "Default")
      (node (ref "DA3") (pin "1") (pinfunction "RG_1") (pintype "bidirectional"))
      (node (ref "R9") (pin "1") (pinfunction "1_1") (pintype "passive"))
    )
    (net (code "39") (name "SG_2_IN") (class "Default")
      (node (ref "DA5") (pin "3") (pinfunction "+_3") (pintype "bidirectional"))
      (node (ref "LR1IN") (pin "TP") (pinfunction "TP_TP") (pintype "input"))
      (node (ref "R16") (pin "1") (pinfunction "1_1") (pintype "passive"))
      (node (ref "R2") (pin "2") (pinfunction "2_2") (pintype "passive"))
      (node (ref "X5") (pin "P$1") (pinfunction "1_P$1") (pintype "passive"))
    )
    (net (code "40") (name "SG_4_IN") (class "Default")
      (node (ref "DA2") (pin "3") (pinfunction "+_3") (pintype "bidirectional"))
      (node (ref "LR2IN") (pin "TP") (pinfunction "TP_TP") (pintype "input"))
      (node (ref "R11") (pin "2") (pinfunction "2_2") (pintype "passive"))
      (node (ref "R17") (pin "1") (pinfunction "1_1") (pintype "passive"))
      (node (ref "X5") (pin "P$2") (pinfunction "2_P$2") (pintype "passive"))
    )
    (net (code "41") (name "SG_6_IN") (class "Default")
      (node (ref "DA3") (pin "3") (pinfunction "+_3") (pintype "bidirectional"))
      (node (ref "R18") (pin "1") (pinfunction "1_1") (pintype "passive"))
      (node (ref "R30") (pin "2") (pinfunction "2_2") (pintype "passive"))
      (node (ref "RR1IN") (pin "TP") (pinfunction "TP_TP") (pintype "input"))
      (node (ref "X5") (pin "P$3") (pinfunction "3_P$3") (pintype "passive"))
    )
    (net (code "42") (name "SG_8_IN") (class "Default")
      (node (ref "DA6") (pin "3") (pinfunction "+_3") (pintype "bidirectional"))
      (node (ref "R21") (pin "1") (pinfunction "1_1") (pintype "passive"))
      (node (ref "R22") (pin "2") (pinfunction "2_2") (pintype "passive"))
      (node (ref "RR2IN") (pin "TP") (pinfunction "TP_TP") (pintype "input"))
      (node (ref "X5") (pin "P$4") (pinfunction "4_P$4") (pintype "passive"))
    )
    (net (code "43") (name "SG_OUT_LR_1") (class "Default")
      (node (ref "DA5") (pin "6") (pinfunction "OUT_6") (pintype "bidirectional"))
      (node (ref "LR1") (pin "TP") (pinfunction "TP_TP") (pintype "input"))
      (node (ref "R12") (pin "2") (pinfunction "2_2") (pintype "passive"))
      (node (ref "X1") (pin "P$8") (pinfunction "8_P$8") (pintype "passive"))
    )
    (net (code "44") (name "SG_OUT_LR_2") (class "Default")
      (node (ref "DA2") (pin "6") (pinfunction "OUT_6") (pintype "bidirectional"))
      (node (ref "LR2") (pin "TP") (pinfunction "TP_TP") (pintype "input"))
      (node (ref "R6") (pin "2") (pinfunction "2_2") (pintype "passive"))
      (node (ref "X1") (pin "P$7") (pinfunction "7_P$7") (pintype "passive"))
    )
    (net (code "45") (name "SG_OUT_RR_1") (class "Default")
      (node (ref "DA3") (pin "6") (pinfunction "OUT_6") (pintype "bidirectional"))
      (node (ref "R5") (pin "2") (pinfunction "2_2") (pintype "passive"))
      (node (ref "RR1") (pin "TP") (pinfunction "TP_TP") (pintype "input"))
      (node (ref "X1") (pin "P$1") (pinfunction "1_P$1") (pintype "passive"))
    )
    (net (code "46") (name "SG_OUT_RR_2") (class "Default")
      (node (ref "DA6") (pin "6") (pinfunction "OUT_6") (pintype "bidirectional"))
      (node (ref "R7") (pin "2") (pinfunction "2_2") (pintype "passive"))
      (node (ref "RR2") (pin "TP") (pinfunction "TP_TP") (pintype "input"))
      (node (ref "X1") (pin "P$2") (pinfunction "2_P$2") (pintype "passive"))
    )
    (net (code "47") (name "SUS_IN_1") (class "Default")
      (node (ref "R27") (pin "1") (pinfunction "1_1") (pintype "passive"))
      (node (ref "R28") (pin "2") (pinfunction "2_2") (pintype "passive"))
      (node (ref "X5") (pin "P$10") (pinfunction "10_P$10") (pintype "passive"))
    )
    (net (code "48") (name "SUS_IN_2") (class "Default")
      (node (ref "R34") (pin "1") (pinfunction "1_1") (pintype "passive"))
      (node (ref "R35") (pin "2") (pinfunction "2_2") (pintype "passive"))
      (node (ref "X5") (pin "P$5") (pinfunction "5_P$5") (pintype "passive"))
    )
    (net (code "49") (name "SUS_RL") (class "Default")
      (node (ref "R32") (pin "2") (pinfunction "2_2") (pintype "passive"))
      (node (ref "R33") (pin "1") (pinfunction "1_1") (pintype "passive"))
      (node (ref "SV2") (pin "1") (pinfunction "1_1") (pintype "passive"))
      (node (ref "X1") (pin "P$6") (pinfunction "6_P$6") (pintype "passive"))
    )
    (net (code "50") (name "SUS_RR") (class "Default")
      (node (ref "R19") (pin "2") (pinfunction "2_2") (pintype "passive"))
      (node (ref "R20") (pin "1") (pinfunction "1_1") (pintype "passive"))
      (node (ref "SV2") (pin "2") (pinfunction "2_2") (pintype "passive"))
      (node (ref "X1") (pin "P$5") (pinfunction "5_P$5") (pintype "passive"))
    )
    (net (code "51") (name "unconnected-(SV5-Pad3)") (class "Default")
      (node (ref "SV5") (pin "3") (pinfunction "3_3") (pintype "passive"))
    )
    (net (code "52") (name "unconnected-(X3-1-PadP$1)") (class "Default")
      (node (ref "X3") (pin "P$1") (pinfunction "1_P$1") (pintype "passive"))
    )
  )
)
